# State_feedback.net
KiCad netlist of a schematic drawn in Altium Designer
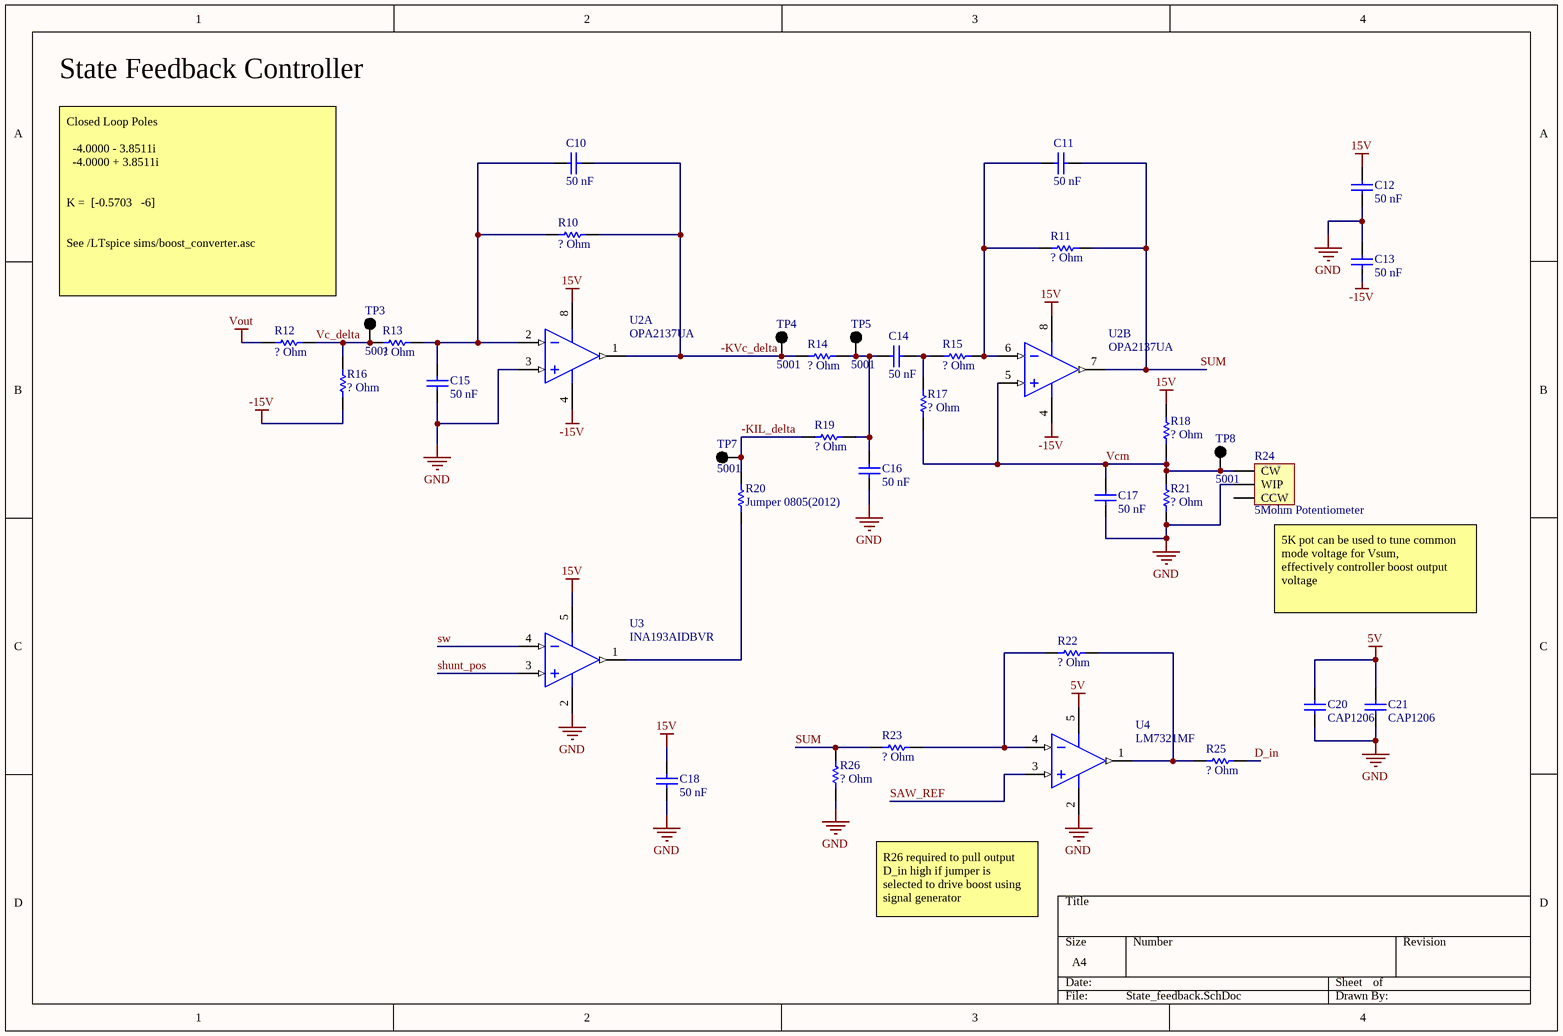
[diagram p0: State_feedback.SchDoc]

(export (version "E")
  (design (tool "Eeschema 10.0.6"))
  (components
    (comp (ref "C10")
      (value "50 nF")
      (footprint "CAPC0805(2012)75_M")
      (description "CAP 0.5pF 50V ±0.1pF 0805 (2012 Metric) Thickness 0.75mm SMD")
      (fields (field (name "TOLERANCE") "Â±0.1pF"))
      (libsource (lib "Altium Content Vault") (part "CMP-1036-00018-1"))
    )
    (comp (ref "C11")
      (value "50 nF")
      (footprint "CAPC0805(2012)75_M")
      (description "CAP 0.5pF 50V ±0.1pF 0805 (2012 Metric) Thickness 0.75mm SMD")
      (fields (field (name "TOLERANCE") "Â±0.1pF"))
      (libsource (lib "Altium Content Vault") (part "CMP-1036-00018-1"))
    )
    (comp (ref "C12")
      (value "50 nF")
      (footprint "CAPC0805(2012)75_M")
      (description "CAP 0.5pF 50V ±0.1pF 0805 (2012 Metric) Thickness 0.75mm SMD")
      (fields (field (name "TOLERANCE") "Â±0.1pF"))
      (libsource (lib "Altium Content Vault") (part "CMP-1036-00018-1"))
    )
    (comp (ref "C13")
      (value "50 nF")
      (footprint "CAPC0805(2012)75_M")
      (description "CAP 0.5pF 50V ±0.1pF 0805 (2012 Metric) Thickness 0.75mm SMD")
      (fields (field (name "TOLERANCE") "Â±0.1pF"))
      (libsource (lib "Altium Content Vault") (part "CMP-1036-00018-1"))
    )
    (comp (ref "C14")
      (value "50 nF")
      (footprint "CAPC0805(2012)75_M")
      (description "CAP 0.5pF 50V ±0.1pF 0805 (2012 Metric) Thickness 0.75mm SMD")
      (fields (field (name "TOLERANCE") "Â±0.1pF"))
      (libsource (lib "Altium Content Vault") (part "CMP-1036-00018-1"))
    )
    (comp (ref "C15")
      (value "50 nF")
      (footprint "CAPC0805(2012)75_M")
      (description "CAP 0.5pF 50V ±0.1pF 0805 (2012 Metric) Thickness 0.75mm SMD")
      (fields (field (name "TOLERANCE") "Â±0.1pF"))
      (libsource (lib "Altium Content Vault") (part "CMP-1036-00018-1"))
    )
    (comp (ref "C16")
      (value "50 nF")
      (footprint "CAPC0805(2012)75_M")
      (description "CAP 0.5pF 50V ±0.1pF 0805 (2012 Metric) Thickness 0.75mm SMD")
      (fields (field (name "TOLERANCE") "Â±0.1pF"))
      (libsource (lib "Altium Content Vault") (part "CMP-1036-00018-1"))
    )
    (comp (ref "C17")
      (value "50 nF")
      (footprint "CAPC0805(2012)75_M")
      (description "CAP 0.5pF 50V ±0.1pF 0805 (2012 Metric) Thickness 0.75mm SMD")
      (fields (field (name "TOLERANCE") "Â±0.1pF"))
      (libsource (lib "Altium Content Vault") (part "CMP-1036-00018-1"))
    )
    (comp (ref "C18")
      (value "50 nF")
      (footprint "CAPC0805(2012)75_M")
      (description "CAP 0.5pF 50V ±0.1pF 0805 (2012 Metric) Thickness 0.75mm SMD")
      (fields (field (name "TOLERANCE") "Â±0.1pF"))
      (libsource (lib "Altium Content Vault") (part "CMP-1036-00018-1"))
    )
    (comp (ref "C20")
      (value "CAP1206")
      (footprint "CAPC1206(3216)150_L")
      (description "1206 (3216 Metric) Chip Capacitor")
      (libsource (lib "Altium Content Vault") (part "CAP_5"))
    )
    (comp (ref "C21")
      (value "CAP1206")
      (footprint "CAPC1206(3216)150_L")
      (description "1206 (3216 Metric) Chip Capacitor")
      (libsource (lib "Altium Content Vault") (part "CAP_5"))
    )
    (comp (ref "R10")
      (value "? Ohm")
      (footprint "RESC0805(2012)_M")
      (description "4R3 0.125W 5% 0805 (2012 Metric)  SMD")
      (fields (field (name "TOLERANCE") "5 %") (field (name "POWER") "0.125 W"))
      (libsource (lib "Altium Content Vault") (part "RES"))
    )
    (comp (ref "R11")
      (value "? Ohm")
      (footprint "RESC0805(2012)_M")
      (description "4R3 0.125W 5% 0805 (2012 Metric)  SMD")
      (fields (field (name "TOLERANCE") "5 %") (field (name "POWER") "0.125 W"))
      (libsource (lib "Altium Content Vault") (part "RES"))
    )
    (comp (ref "R12")
      (value "? Ohm")
      (footprint "RESC0805(2012)_M")
      (description "4R3 0.125W 5% 0805 (2012 Metric)  SMD")
      (fields (field (name "TOLERANCE") "5 %") (field (name "POWER") "0.125 W"))
      (libsource (lib "Altium Content Vault") (part "RES"))
    )
    (comp (ref "R13")
      (value "? Ohm")
      (footprint "RESC0805(2012)_M")
      (description "4R3 0.125W 5% 0805 (2012 Metric)  SMD")
      (fields (field (name "TOLERANCE") "5 %") (field (name "POWER") "0.125 W"))
      (libsource (lib "Altium Content Vault") (part "RES"))
    )
    (comp (ref "R14")
      (value "? Ohm")
      (footprint "RESC0805(2012)_M")
      (description "4R3 0.125W 5% 0805 (2012 Metric)  SMD")
      (fields (field (name "TOLERANCE") "5 %") (field (name "POWER") "0.125 W"))
      (libsource (lib "Altium Content Vault") (part "RES"))
    )
    (comp (ref "R15")
      (value "? Ohm")
      (footprint "RESC0805(2012)_M")
      (description "4R3 0.125W 5% 0805 (2012 Metric)  SMD")
      (fields (field (name "TOLERANCE") "5 %") (field (name "POWER") "0.125 W"))
      (libsource (lib "Altium Content Vault") (part "RES"))
    )
    (comp (ref "R16")
      (value "? Ohm")
      (footprint "RESC0805(2012)_M")
      (description "4R3 0.125W 5% 0805 (2012 Metric)  SMD")
      (fields (field (name "TOLERANCE") "5 %") (field (name "POWER") "0.125 W"))
      (libsource (lib "Altium Content Vault") (part "RES"))
    )
    (comp (ref "R17")
      (value "? Ohm")
      (footprint "RESC0805(2012)_M")
      (description "4R3 0.125W 5% 0805 (2012 Metric)  SMD")
      (fields (field (name "TOLERANCE") "5 %") (field (name "POWER") "0.125 W"))
      (libsource (lib "Altium Content Vault") (part "RES"))
    )
    (comp (ref "R18")
      (value "? Ohm")
      (footprint "RESC0805(2012)_M")
      (description "4R3 0.125W 5% 0805 (2012 Metric)  SMD")
      (fields (field (name "TOLERANCE") "5 %") (field (name "POWER") "0.125 W"))
      (libsource (lib "Altium Content Vault") (part "RES"))
    )
    (comp (ref "R19")
      (value "? Ohm")
      (footprint "RESC0805(2012)_M")
      (description "4R3 0.125W 5% 0805 (2012 Metric)  SMD")
      (fields (field (name "TOLERANCE") "5 %") (field (name "POWER") "0.125 W"))
      (libsource (lib "Altium Content Vault") (part "RES"))
    )
    (comp (ref "R20")
      (value "Jumper 0805(2012)")
      (footprint "RESC0805(2012)_N")
      (description "Jumper 0805 (2012 Metric)")
      (fields (field (name "TOLERANCE") "None"))
      (libsource (lib "Altium Content Vault") (part "RES"))
    )
    (comp (ref "R21")
      (value "? Ohm")
      (footprint "RESC0805(2012)_M")
      (description "4R3 0.125W 5% 0805 (2012 Metric)  SMD")
      (fields (field (name "TOLERANCE") "5 %") (field (name "POWER") "0.125 W"))
      (libsource (lib "Altium Content Vault") (part "RES"))
    )
    (comp (ref "R22")
      (value "? Ohm")
      (footprint "RESC0805(2012)_M")
      (description "4R3 0.125W 5% 0805 (2012 Metric)  SMD")
      (fields (field (name "TOLERANCE") "5 %") (field (name "POWER") "0.125 W"))
      (libsource (lib "Altium Content Vault") (part "RES"))
    )
    (comp (ref "R23")
      (value "? Ohm")
      (footprint "RESC0805(2012)_M")
      (description "4R3 0.125W 5% 0805 (2012 Metric)  SMD")
      (fields (field (name "TOLERANCE") "5 %") (field (name "POWER") "0.125 W"))
      (libsource (lib "Altium Content Vault") (part "RES"))
    )
    (comp (ref "R24")
      (value "5Mohm Potentiometer")
      (footprint "5k_pot")
      (description "3296W-1-505LF")
      (libsource (lib "Boost_lib") (part "5Mohm Potentiometer"))
    )
    (comp (ref "R25")
      (value "? Ohm")
      (footprint "RESC0805(2012)_M")
      (description "4R3 0.125W 5% 0805 (2012 Metric)  SMD")
      (fields (field (name "TOLERANCE") "5 %") (field (name "POWER") "0.125 W"))
      (libsource (lib "Altium Content Vault") (part "RES"))
    )
    (comp (ref "R26")
      (value "? Ohm")
      (footprint "RESC0805(2012)_M")
      (description "4R3 0.125W 5% 0805 (2012 Metric)  SMD")
      (fields (field (name "TOLERANCE") "5 %") (field (name "POWER") "0.125 W"))
      (libsource (lib "Altium Content Vault") (part "CMP-1013-00017-1"))
    )
    (comp (ref "TP3")
      (value "5001")
      (footprint "KSTN-5001")
      (description "Test Point, Black, 1-Pin THD, RoHS, Bulk")
      (fields (field (name "MANUFACTURER") "Keystone"))
      (libsource (lib "Altium Content Vault") (part "KSTN-TP-5001"))
    )
    (comp (ref "TP4")
      (value "5001")
      (footprint "KSTN-5001")
      (description "Test Point, Black, 1-Pin THD, RoHS, Bulk")
      (fields (field (name "MANUFACTURER") "Keystone"))
      (libsource (lib "Altium Content Vault") (part "KSTN-TP-5001"))
    )
    (comp (ref "TP5")
      (value "5001")
      (footprint "KSTN-5001")
      (description "Test Point, Black, 1-Pin THD, RoHS, Bulk")
      (fields (field (name "MANUFACTURER") "Keystone"))
      (libsource (lib "Altium Content Vault") (part "KSTN-TP-5001"))
    )
    (comp (ref "TP7")
      (value "5001")
      (footprint "KSTN-5001")
      (description "Test Point, Black, 1-Pin THD, RoHS, Bulk")
      (fields (field (name "MANUFACTURER") "Keystone"))
      (libsource (lib "Altium Content Vault") (part "CMP-2000-05181-1"))
    )
    (comp (ref "TP8")
      (value "5001")
      (footprint "KSTN-5001")
      (description "Test Point, Black, 1-Pin THD, RoHS, Bulk")
      (fields (field (name "MANUFACTURER") "Keystone"))
      (libsource (lib "Altium Content Vault") (part "KSTN-TP-5001"))
    )
    (comp (ref "U2")
      (value "OPA2137UA")
      (footprint "D0008A_M")
      (fields (field (name "MANUFACTURER") "Texas Instruments"))
      (libsource (lib "Altium Content Vault") (part "TI-AMP-D6-2-8_B"))
    )
    (comp (ref "U3")
      (value "INA193AIDBVR")
      (footprint "DBV0005A_M")
      (fields (field (name "MANUFACTURER") "Texas Instruments"))
      (libsource (lib "Altium Content Vault") (part "TI-INA1XXDBV5"))
    )
    (comp (ref "U4")
      (value "LM7321MF")
      (footprint "MF05A_L")
      (fields (field (name "MANUFACTURER") "National Semiconductor"))
      (libsource (lib "Altium Content Vault") (part "AMP-OPA-LM7121-5"))
    )
  )
  (nets
    (net (code "1") (name "-15V") (class "Default")
      (node (ref "C13") (pin "2") (pinfunction "2_2") (pintype "passive"))
      (node (ref "R16") (pin "1") (pinfunction "1_1") (pintype "passive"))
      (node (ref "U2") (pin "4") (pinfunction "V-_4") (pintype "power_in"))
    )
    (net (code "2") (name "/-KIL_delta") (class "Default")
      (node (ref "R19") (pin "1") (pinfunction "1_1") (pintype "passive"))
      (node (ref "R20") (pin "2") (pinfunction "2_2") (pintype "passive"))
      (node (ref "TP7") (pin "1") (pintype "passive"))
    )
    (net (code "3") (name "/-KVc_delta") (class "Default")
      (node (ref "C10") (pin "2") (pinfunction "2_2") (pintype "passive"))
      (node (ref "R10") (pin "2") (pinfunction "2_2") (pintype "passive"))
      (node (ref "R14") (pin "1") (pinfunction "1_1") (pintype "passive"))
      (node (ref "TP4") (pin "1") (pintype "passive"))
      (node (ref "U2") (pin "1") (pinfunction "OUT_A_1") (pintype "output"))
    )
    (net (code "4") (name "/D_in") (class "Default")
      (node (ref "R25") (pin "2") (pinfunction "2_2") (pintype "passive"))
    )
    (net (code "5") (name "/SAW_REF") (class "Default")
      (node (ref "U4") (pin "3") (pinfunction "IN+_3") (pintype "input"))
    )
    (net (code "6") (name "/SUM") (class "Default")
      (node (ref "C11") (pin "2") (pinfunction "2_2") (pintype "passive"))
      (node (ref "R11") (pin "2") (pinfunction "2_2") (pintype "passive"))
      (node (ref "R23") (pin "1") (pinfunction "1_1") (pintype "passive"))
      (node (ref "R26") (pin "2") (pinfunction "2_2") (pintype "passive"))
      (node (ref "U2") (pin "7") (pinfunction "OUT_B_7") (pintype "output"))
    )
    (net (code "7") (name "/Vc_delta") (class "Default")
      (node (ref "R12") (pin "2") (pinfunction "2_2") (pintype "passive"))
      (node (ref "R13") (pin "1") (pinfunction "1_1") (pintype "passive"))
      (node (ref "R16") (pin "2") (pinfunction "2_2") (pintype "passive"))
      (node (ref "TP3") (pin "1") (pintype "passive"))
    )
    (net (code "8") (name "/Vcm") (class "Default")
      (node (ref "C17") (pin "2") (pinfunction "2_2") (pintype "passive"))
      (node (ref "R17") (pin "1") (pinfunction "1_1") (pintype "passive"))
      (node (ref "R18") (pin "1") (pinfunction "1_1") (pintype "passive"))
      (node (ref "R21") (pin "2") (pinfunction "2_2") (pintype "passive"))
      (node (ref "R24") (pin "1") (pinfunction "CW_1") (pintype "passive"))
      (node (ref "TP8") (pin "1") (pintype "passive"))
      (node (ref "U2") (pin "5") (pinfunction "IN_B+_5") (pintype "input"))
    )
    (net (code "9") (name "/shunt_pos") (class "Default")
      (node (ref "U3") (pin "3") (pinfunction "VIN+_3") (pintype "input"))
    )
    (net (code "10") (name "/sw") (class "Default")
      (node (ref "U3") (pin "4") (pinfunction "VIN-_4") (pintype "input"))
    )
    (net (code "11") (name "5V") (class "Default")
      (node (ref "C20") (pin "2") (pinfunction "2_2") (pintype "passive"))
      (node (ref "C21") (pin "2") (pinfunction "2_2") (pintype "passive"))
      (node (ref "U4") (pin "5") (pinfunction "V+_5") (pintype "power_in"))
    )
    (net (code "12") (name "15V") (class "Default")
      (node (ref "C12") (pin "1") (pinfunction "1_1") (pintype "passive"))
      (node (ref "C18") (pin "1") (pinfunction "1_1") (pintype "passive"))
      (node (ref "R18") (pin "2") (pinfunction "2_2") (pintype "passive"))
      (node (ref "U2") (pin "8") (pinfunction "V+_8") (pintype "power_in"))
      (node (ref "U3") (pin "5") (pinfunction "V+_5") (pintype "power_in"))
    )
    (net (code "13") (name "GND") (class "Default")
      (node (ref "C12") (pin "2") (pinfunction "2_2") (pintype "passive"))
      (node (ref "C13") (pin "1") (pinfunction "1_1") (pintype "passive"))
      (node (ref "C15") (pin "2") (pinfunction "2_2") (pintype "passive"))
      (node (ref "C16") (pin "1") (pinfunction "1_1") (pintype "passive"))
      (node (ref "C17") (pin "1") (pinfunction "1_1") (pintype "passive"))
      (node (ref "C18") (pin "2") (pinfunction "2_2") (pintype "passive"))
      (node (ref "C20") (pin "1") (pinfunction "1_1") (pintype "passive"))
      (node (ref "C21") (pin "1") (pinfunction "1_1") (pintype "passive"))
      (node (ref "R21") (pin "1") (pinfunction "1_1") (pintype "passive"))
      (node (ref "R24") (pin "2") (pinfunction "WIP_2") (pintype "passive"))
      (node (ref "R26") (pin "1") (pinfunction "1_1") (pintype "passive"))
      (node (ref "U2") (pin "3") (pinfunction "IN_A+_3") (pintype "input"))
      (node (ref "U3") (pin "2") (pinfunction "GND_2") (pintype "power_in"))
      (node (ref "U4") (pin "2") (pinfunction "V-_2") (pintype "power_in"))
    )
    (net (code "14") (name "Net-(C14-Pad1)") (class "Default")
      (node (ref "C14") (pin "1") (pinfunction "1_1") (pintype "passive"))
      (node (ref "C16") (pin "2") (pinfunction "2_2") (pintype "passive"))
      (node (ref "R14") (pin "2") (pinfunction "2_2") (pintype "passive"))
      (node (ref "R19") (pin "2") (pinfunction "2_2") (pintype "passive"))
      (node (ref "TP5") (pin "1") (pintype "passive"))
    )
    (net (code "15") (name "Net-(C14-Pad2)") (class "Default")
      (node (ref "C14") (pin "2") (pinfunction "2_2") (pintype "passive"))
      (node (ref "R15") (pin "1") (pinfunction "1_1") (pintype "passive"))
      (node (ref "R17") (pin "2") (pinfunction "2_2") (pintype "passive"))
    )
    (net (code "16") (name "Net-(U2A-IN_A-)") (class "Default")
      (node (ref "C10") (pin "1") (pinfunction "1_1") (pintype "passive"))
      (node (ref "C15") (pin "1") (pinfunction "1_1") (pintype "passive"))
      (node (ref "R10") (pin "1") (pinfunction "1_1") (pintype "passive"))
      (node (ref "R13") (pin "2") (pinfunction "2_2") (pintype "passive"))
      (node (ref "U2") (pin "2") (pinfunction "IN_A-_2") (pintype "input"))
    )
    (net (code "17") (name "Net-(U2B-IN_B-)") (class "Default")
      (node (ref "C11") (pin "1") (pinfunction "1_1") (pintype "passive"))
      (node (ref "R11") (pin "1") (pinfunction "1_1") (pintype "passive"))
      (node (ref "R15") (pin "2") (pinfunction "2_2") (pintype "passive"))
      (node (ref "U2") (pin "6") (pinfunction "IN_B-_6") (pintype "input"))
    )
    (net (code "18") (name "Net-(U3-OUT)") (class "Default")
      (node (ref "R20") (pin "1") (pinfunction "1_1") (pintype "passive"))
      (node (ref "U3") (pin "1") (pinfunction "OUT_1") (pintype "output"))
    )
    (net (code "19") (name "Net-(U4-IN-)") (class "Default")
      (node (ref "R22") (pin "1") (pinfunction "1_1") (pintype "passive"))
      (node (ref "R23") (pin "2") (pinfunction "2_2") (pintype "passive"))
      (node (ref "U4") (pin "4") (pinfunction "IN-_4") (pintype "input"))
    )
    (net (code "20") (name "Net-(U4-OUT)") (class "Default")
      (node (ref "R22") (pin "2") (pinfunction "2_2") (pintype "passive"))
      (node (ref "R25") (pin "1") (pinfunction "1_1") (pintype "passive"))
      (node (ref "U4") (pin "1") (pinfunction "OUT_1") (pintype "output"))
    )
    (net (code "21") (name "Vout") (class "Default")
      (node (ref "R12") (pin "1") (pinfunction "1_1") (pintype "passive"))
    )
    (net (code "22") (name "unconnected-(R24-CCW-Pad3)") (class "Default")
      (node (ref "R24") (pin "3") (pinfunction "CCW_3") (pintype "passive"))
    )
  )
)
